# UniRF-Rev02.net
KiCad netlist of a schematic drawn in EAGLE
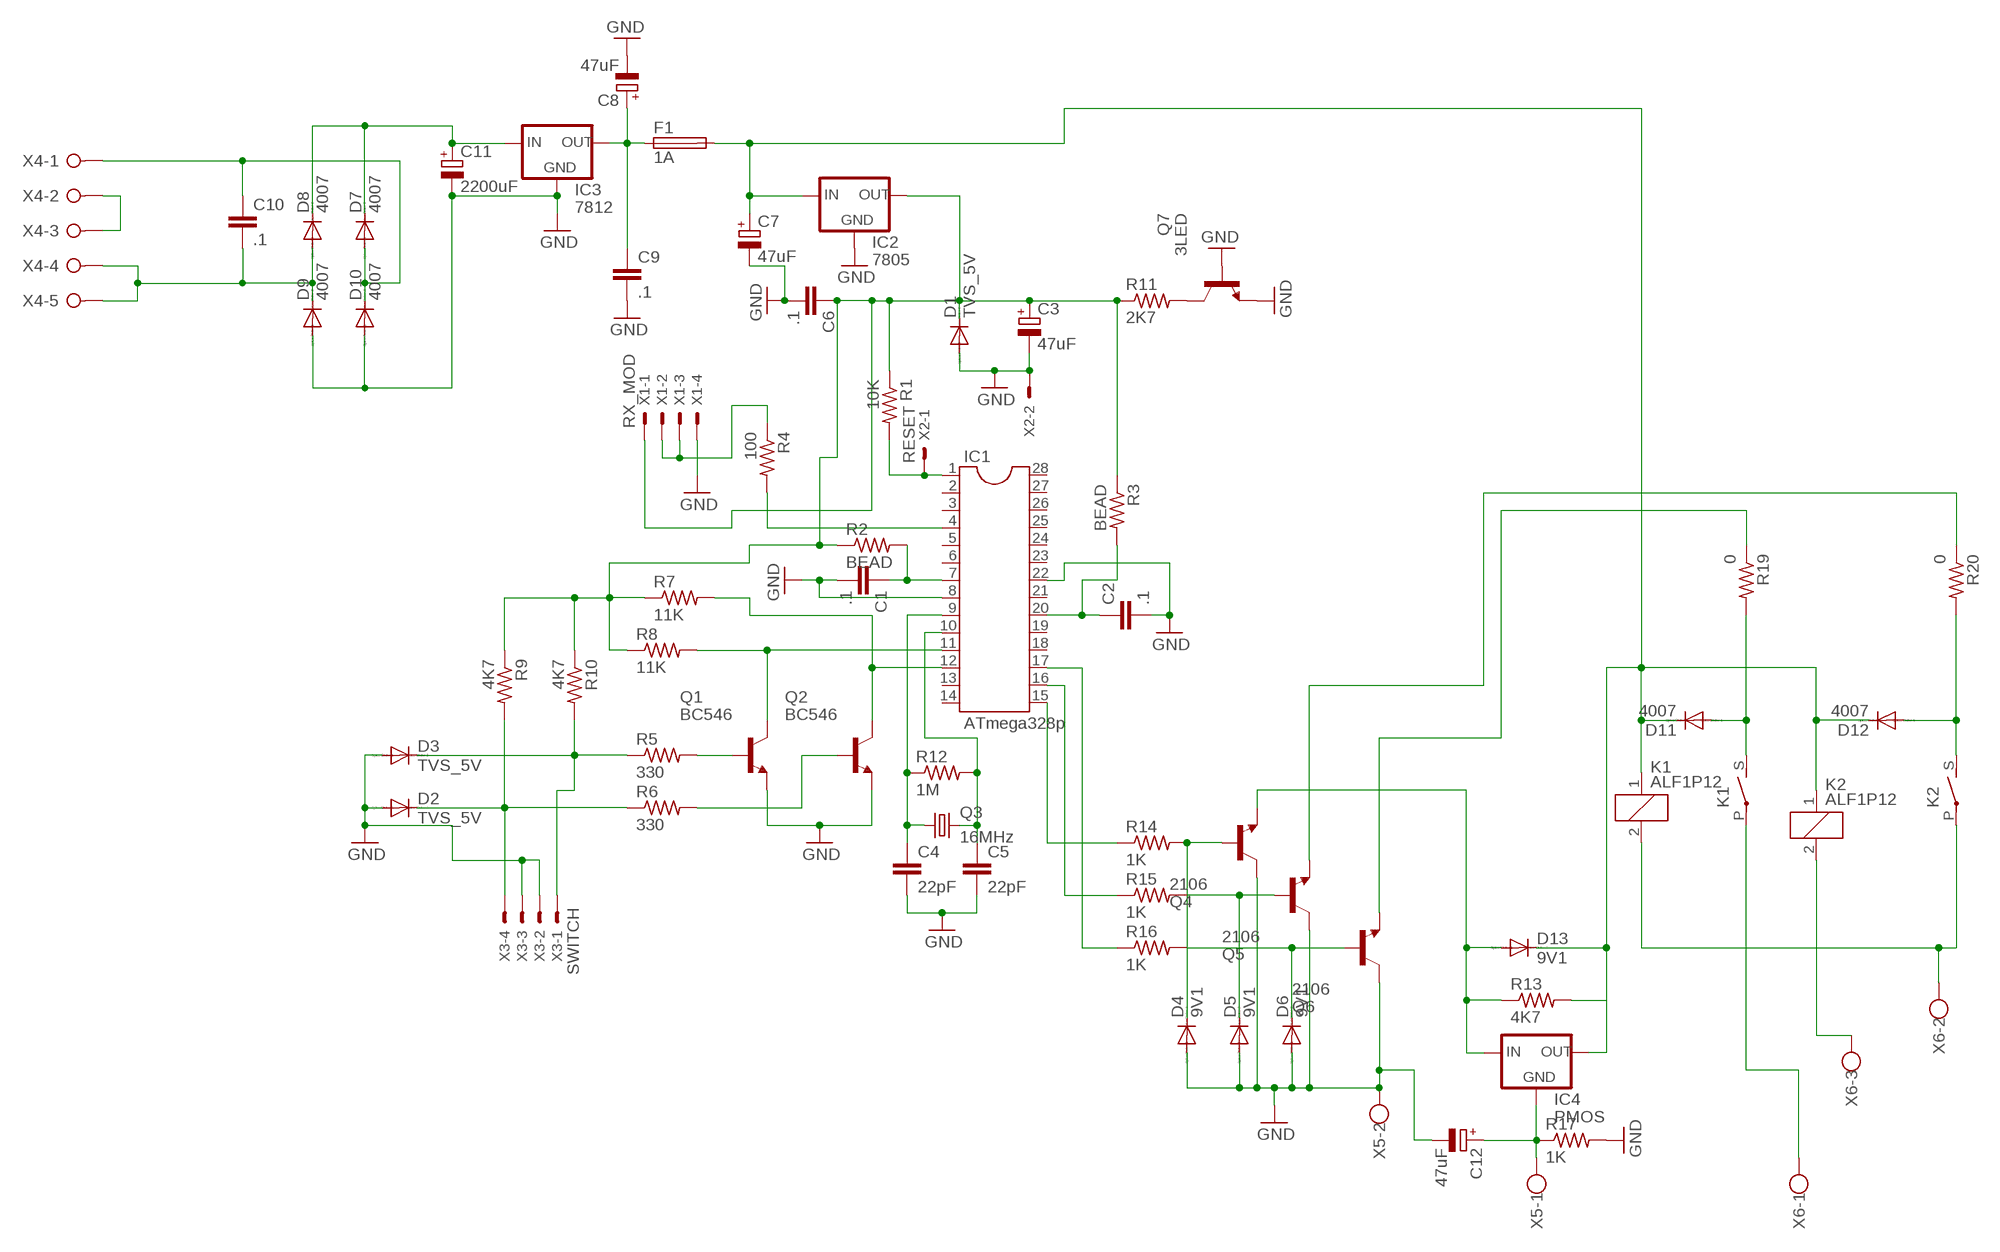
[diagram p0: schematic, sheet 1]

(export (version "E")
  (design (tool "Eeschema 10.0.6"))
  (components
    (comp (ref "C1")
      (value ".1")
      (footprint "eagle-import:C1210K")
      (libsource (lib "eagle-import") (part "C-EUC1210K"))
    )
    (comp (ref "C2")
      (value ".1")
      (footprint "eagle-import:C1210K")
      (libsource (lib "eagle-import") (part "C-EUC1210K"))
    )
    (comp (ref "C3")
      (value "47uF")
      (footprint "eagle-import:E5-8,5")
      (libsource (lib "eagle-import") (part "CPOL-EUE5-8.5"))
    )
    (comp (ref "C4")
      (value "22pF")
      (footprint "eagle-import:C1210K")
      (libsource (lib "eagle-import") (part "C-EUC1210K"))
    )
    (comp (ref "C5")
      (value "22pF")
      (footprint "eagle-import:C1210K")
      (libsource (lib "eagle-import") (part "C-EUC1210K"))
    )
    (comp (ref "C6")
      (value ".1")
      (footprint "eagle-import:C1210K")
      (libsource (lib "eagle-import") (part "C-EUC1210K"))
    )
    (comp (ref "C7")
      (value "47uF")
      (footprint "eagle-import:E5-8,5")
      (libsource (lib "eagle-import") (part "CPOL-EUE5-8.5"))
    )
    (comp (ref "C8")
      (value "47uF")
      (footprint "eagle-import:E5-8,5")
      (libsource (lib "eagle-import") (part "CPOL-EUE5-8.5"))
    )
    (comp (ref "C9")
      (value ".1")
      (footprint "eagle-import:C1210K")
      (libsource (lib "eagle-import") (part "C-EUC1210K"))
    )
    (comp (ref "C10")
      (value ".1")
      (footprint "eagle-import:C075-042X103")
      (libsource (lib "eagle-import") (part "C-EU075-042X103"))
    )
    (comp (ref "C11")
      (value "2200uF")
      (footprint "eagle-import:E7,5-18")
      (libsource (lib "eagle-import") (part "CPOL-EUE7.5-18"))
    )
    (comp (ref "C12")
      (value "47uF")
      (footprint "eagle-import:E5-8,5")
      (libsource (lib "eagle-import") (part "CPOL-EUE5-8.5"))
    )
    (comp (ref "D1")
      (value "TVS_5V")
      (footprint "eagle-import:DO35-10")
      (libsource (lib "eagle-import") (part "1N4148DO35-10"))
    )
    (comp (ref "D2")
      (value "TVS_5V")
      (footprint "eagle-import:DO35-10")
      (libsource (lib "eagle-import") (part "1N4148DO35-10"))
    )
    (comp (ref "D3")
      (value "TVS_5V")
      (footprint "eagle-import:DO35-10")
      (libsource (lib "eagle-import") (part "1N4148DO35-10"))
    )
    (comp (ref "D4")
      (value "9V1")
      (footprint "eagle-import:DO35-7")
      (libsource (lib "eagle-import") (part "1N4148DO35-7"))
    )
    (comp (ref "D5")
      (value "9V1")
      (footprint "eagle-import:DO35-7")
      (libsource (lib "eagle-import") (part "1N4148DO35-7"))
    )
    (comp (ref "D6")
      (value "9V1")
      (footprint "eagle-import:DO35-7")
      (libsource (lib "eagle-import") (part "1N4148DO35-7"))
    )
    (comp (ref "D7")
      (value "4007")
      (footprint "eagle-import:DO204-10")
      (libsource (lib "eagle-import") (part "1N5059"))
    )
    (comp (ref "D8")
      (value "4007")
      (footprint "eagle-import:DO204-10")
      (libsource (lib "eagle-import") (part "1N5059"))
    )
    (comp (ref "D9")
      (value "4007")
      (footprint "eagle-import:DO204-10")
      (libsource (lib "eagle-import") (part "1N5059"))
    )
    (comp (ref "D10")
      (value "4007")
      (footprint "eagle-import:DO204-10")
      (libsource (lib "eagle-import") (part "1N5059"))
    )
    (comp (ref "D11")
      (value "4007")
      (footprint "eagle-import:DO35-10")
      (libsource (lib "eagle-import") (part "1N4148DO35-10"))
    )
    (comp (ref "D12")
      (value "4007")
      (footprint "eagle-import:DO35-10")
      (libsource (lib "eagle-import") (part "1N4148DO35-10"))
    )
    (comp (ref "D13")
      (value "9V1")
      (footprint "eagle-import:DO35-10")
      (libsource (lib "eagle-import") (part "1N4148DO35-10"))
    )
    (comp (ref "F1")
      (value "1A")
      (footprint "eagle-import:19560")
      (fields (field (name "MPN") "56000001009"))
      (libsource (lib "eagle-import") (part "19560"))
    )
    (comp (ref "IC1")
      (value "ATmega328p")
      (footprint "eagle-import:DIL28-3")
      (libsource (lib "eagle-import") (part "DIL28-3"))
    )
    (comp (ref "IC2")
      (value "7805")
      (footprint "eagle-import:78XXS")
      (libsource (lib "eagle-import") (part "78XXS"))
    )
    (comp (ref "IC3")
      (value "7812")
      (footprint "eagle-import:78XXS")
      (libsource (lib "eagle-import") (part "78XXS"))
    )
    (comp (ref "IC4")
      (value "PMOS")
      (footprint "eagle-import:78XXS")
      (libsource (lib "eagle-import") (part "78XXS"))
    )
    (comp (ref "K1")
      (value "ALF1P12")
      (footprint "eagle-import:G2RA")
      (libsource (lib "eagle-import") (part "G2RA"))
    )
    (comp (ref "K2")
      (value "ALF1P12")
      (footprint "eagle-import:G2RA")
      (libsource (lib "eagle-import") (part "G2RA"))
    )
    (comp (ref "Q1")
      (value "BC546")
      (footprint "eagle-import:TO92-EBC")
      (libsource (lib "eagle-import") (part "BC546A"))
    )
    (comp (ref "Q2")
      (value "BC546")
      (footprint "eagle-import:TO92-EBC")
      (libsource (lib "eagle-import") (part "BC546A"))
    )
    (comp (ref "Q3")
      (value "16MHz")
      (footprint "eagle-import:HC49_S")
      (libsource (lib "eagle-import") (part "CRYSTALHC49S"))
    )
    (comp (ref "Q4")
      (value "2106")
      (footprint "eagle-import:TO92-EBC")
      (libsource (lib "eagle-import") (part "BC546A"))
    )
    (comp (ref "Q5")
      (value "2106")
      (footprint "eagle-import:TO92-EBC")
      (libsource (lib "eagle-import") (part "BC546A"))
    )
    (comp (ref "Q6")
      (value "2106")
      (footprint "eagle-import:TO92-EBC")
      (libsource (lib "eagle-import") (part "BC546A"))
    )
    (comp (ref "Q7")
      (value "3LED")
      (footprint "eagle-import:TO92-EBC")
      (libsource (lib "eagle-import") (part "BC546A"))
    )
    (comp (ref "R1")
      (value "10K")
      (footprint "eagle-import:0309_10")
      (libsource (lib "eagle-import") (part "R-US_0309/10"))
    )
    (comp (ref "R2")
      (value "BEAD")
      (footprint "eagle-import:0309_10")
      (libsource (lib "eagle-import") (part "R-US_0309/10"))
    )
    (comp (ref "R3")
      (value "BEAD")
      (footprint "eagle-import:0309_12")
      (libsource (lib "eagle-import") (part "R-US_0309/12"))
    )
    (comp (ref "R4")
      (value "100")
      (footprint "eagle-import:0309_10")
      (libsource (lib "eagle-import") (part "R-US_0309/10"))
    )
    (comp (ref "R5")
      (value "330")
      (footprint "eagle-import:0309_10")
      (libsource (lib "eagle-import") (part "R-US_0309/10"))
    )
    (comp (ref "R6")
      (value "330")
      (footprint "eagle-import:0309_10")
      (libsource (lib "eagle-import") (part "R-US_0309/10"))
    )
    (comp (ref "R7")
      (value "11K")
      (footprint "eagle-import:0309_10")
      (libsource (lib "eagle-import") (part "R-US_0309/10"))
    )
    (comp (ref "R8")
      (value "11K")
      (footprint "eagle-import:0309_10")
      (libsource (lib "eagle-import") (part "R-US_0309/10"))
    )
    (comp (ref "R9")
      (value "4K7")
      (footprint "eagle-import:0309_10")
      (libsource (lib "eagle-import") (part "R-US_0309/10"))
    )
    (comp (ref "R10")
      (value "4K7")
      (footprint "eagle-import:0309_10")
      (libsource (lib "eagle-import") (part "R-US_0309/10"))
    )
    (comp (ref "R11")
      (value "2K7")
      (footprint "eagle-import:0309_10")
      (libsource (lib "eagle-import") (part "R-US_0309/10"))
    )
    (comp (ref "R12")
      (value "1M")
      (footprint "eagle-import:0309V")
      (libsource (lib "eagle-import") (part "R-US_0309/V"))
    )
    (comp (ref "R13")
      (value "4K7")
      (footprint "eagle-import:0309_10")
      (libsource (lib "eagle-import") (part "R-US_0309/10"))
    )
    (comp (ref "R14")
      (value "1K")
      (footprint "eagle-import:R1210")
      (libsource (lib "eagle-import") (part "R-US_R1210"))
    )
    (comp (ref "R15")
      (value "1K")
      (footprint "eagle-import:R1210")
      (libsource (lib "eagle-import") (part "R-US_R1210"))
    )
    (comp (ref "R16")
      (value "1K")
      (footprint "eagle-import:R1210")
      (libsource (lib "eagle-import") (part "R-US_R1210"))
    )
    (comp (ref "R17")
      (value "1K")
      (footprint "eagle-import:0309_12")
      (libsource (lib "eagle-import") (part "R-US_0309/12"))
    )
    (comp (ref "R19")
      (value "0")
      (footprint "eagle-import:0207_12")
      (libsource (lib "eagle-import") (part "R-US_0207/12"))
    )
    (comp (ref "R20")
      (value "0")
      (footprint "eagle-import:0207_12")
      (libsource (lib "eagle-import") (part "R-US_0207/12"))
    )
    (comp (ref "X1")
      (value "RX_MOD")
      (footprint "eagle-import:22-23-2041")
      (fields (field (name "MF") "MOLEX") (field (name "MPN") "22-23-2041"))
      (libsource (lib "eagle-import") (part "22-23-2041"))
    )
    (comp (ref "X2")
      (value "RESET")
      (footprint "eagle-import:22-23-2021")
      (fields (field (name "MF") "MOLEX") (field (name "MPN") "22-23-2021"))
      (libsource (lib "eagle-import") (part "22-23-2021"))
    )
    (comp (ref "X3")
      (value "SWITCH")
      (footprint "eagle-import:22-23-2041")
      (fields (field (name "MF") "MOLEX") (field (name "MPN") "22-23-2041"))
      (libsource (lib "eagle-import") (part "22-23-2041"))
    )
    (comp (ref "X4")
      (value "W237-05P")
      (footprint "eagle-import:W237-5P")
      (libsource (lib "eagle-import") (part "W237-05P"))
    )
    (comp (ref "X5")
      (value "W237-102")
      (footprint "eagle-import:W237-102")
      (fields (field (name "MPN") "237-102"))
      (libsource (lib "eagle-import") (part "W237-102"))
    )
    (comp (ref "X6")
      (value "W237-103")
      (footprint "eagle-import:W237-103")
      (fields (field (name "MPN") "237-103"))
      (libsource (lib "eagle-import") (part "W237-103"))
    )
  )
  (nets
    (net (code "1") (name "GND") (class "Default")
      (node (ref "C1") (pin "2") (pinfunction "2_2") (pintype "passive"))
      (node (ref "C11") (pin "-") (pinfunction "-_-") (pintype "passive"))
      (node (ref "C12") (pin "-") (pinfunction "-_-") (pintype "passive"))
      (node (ref "C2") (pin "2") (pinfunction "2_2") (pintype "passive"))
      (node (ref "C3") (pin "-") (pinfunction "-_-") (pintype "passive"))
      (node (ref "C4") (pin "2") (pinfunction "2_2") (pintype "passive"))
      (node (ref "C5") (pin "2") (pinfunction "2_2") (pintype "passive"))
      (node (ref "C6") (pin "2") (pinfunction "2_2") (pintype "passive"))
      (node (ref "C7") (pin "-") (pinfunction "-_-") (pintype "passive"))
      (node (ref "C8") (pin "-") (pinfunction "-_-") (pintype "passive"))
      (node (ref "C9") (pin "2") (pinfunction "2_2") (pintype "passive"))
      (node (ref "D1") (pin "A") (pinfunction "A_A") (pintype "passive"))
      (node (ref "D10") (pin "A") (pinfunction "A_A") (pintype "passive"))
      (node (ref "D2") (pin "A") (pinfunction "A_A") (pintype "passive"))
      (node (ref "D3") (pin "A") (pinfunction "A_A") (pintype "passive"))
      (node (ref "D4") (pin "A") (pinfunction "A_A") (pintype "passive"))
      (node (ref "D5") (pin "A") (pinfunction "A_A") (pintype "passive"))
      (node (ref "D6") (pin "A") (pinfunction "A_A") (pintype "passive"))
      (node (ref "D9") (pin "A") (pinfunction "A_A") (pintype "passive"))
      (node (ref "IC1") (pin "22") (pinfunction "22_22") (pintype "passive"))
      (node (ref "IC1") (pin "8") (pinfunction "8_8") (pintype "passive"))
      (node (ref "IC2") (pin "GND") (pinfunction "GND_GND") (pintype "input"))
      (node (ref "IC3") (pin "GND") (pinfunction "GND_GND") (pintype "input"))
      (node (ref "Q1") (pin "E") (pinfunction "E_E") (pintype "passive"))
      (node (ref "Q2") (pin "E") (pinfunction "E_E") (pintype "passive"))
      (node (ref "Q4") (pin "C") (pinfunction "C_C") (pintype "passive"))
      (node (ref "Q5") (pin "C") (pinfunction "C_C") (pintype "passive"))
      (node (ref "Q6") (pin "C") (pinfunction "C_C") (pintype "passive"))
      (node (ref "Q7") (pin "B") (pinfunction "B_B") (pintype "passive"))
      (node (ref "Q7") (pin "E") (pinfunction "E_E") (pintype "passive"))
      (node (ref "R17") (pin "2") (pinfunction "2_2") (pintype "passive"))
      (node (ref "X1") (pin "4") (pinfunction "S_4") (pintype "passive"))
      (node (ref "X2") (pin "2") (pinfunction "S_2") (pintype "passive"))
      (node (ref "X3") (pin "2") (pinfunction "S_2") (pintype "passive"))
      (node (ref "X3") (pin "3") (pinfunction "S_3") (pintype "passive"))
      (node (ref "X5") (pin "2") (pinfunction "KL_2") (pintype "passive"))
    )
    (net (code "2") (name "Net-(C1-Pad1)") (class "Default")
      (node (ref "C1") (pin "1") (pinfunction "1_1") (pintype "passive"))
      (node (ref "IC1") (pin "7") (pinfunction "7_7") (pintype "passive"))
      (node (ref "R2") (pin "2") (pinfunction "2_2") (pintype "passive"))
    )
    (net (code "3") (name "Net-(C2-Pad1)") (class "Default")
      (node (ref "C2") (pin "1") (pinfunction "1_1") (pintype "passive"))
      (node (ref "IC1") (pin "20") (pinfunction "20_20") (pintype "passive"))
      (node (ref "R3") (pin "2") (pinfunction "2_2") (pintype "passive"))
    )
    (net (code "4") (name "Net-(C4-Pad1)") (class "Default")
      (node (ref "C4") (pin "1") (pinfunction "1_1") (pintype "passive"))
      (node (ref "IC1") (pin "9") (pinfunction "9_9") (pintype "passive"))
      (node (ref "Q3") (pin "1") (pinfunction "1_1") (pintype "passive"))
      (node (ref "R12") (pin "1") (pinfunction "1_1") (pintype "passive"))
    )
    (net (code "5") (name "Net-(C5-Pad1)") (class "Default")
      (node (ref "C5") (pin "1") (pinfunction "1_1") (pintype "passive"))
      (node (ref "IC1") (pin "10") (pinfunction "10_10") (pintype "passive"))
      (node (ref "Q3") (pin "2") (pinfunction "2_2") (pintype "passive"))
      (node (ref "R12") (pin "2") (pinfunction "2_2") (pintype "passive"))
    )
    (net (code "6") (name "Net-(C7-Pad+)") (class "Default")
      (node (ref "C7") (pin "+") (pinfunction "+_+") (pintype "passive"))
      (node (ref "D11") (pin "C") (pinfunction "C_C") (pintype "passive"))
      (node (ref "D12") (pin "C") (pinfunction "C_C") (pintype "passive"))
      (node (ref "D13") (pin "C") (pinfunction "C_C") (pintype "passive"))
      (node (ref "F1") (pin "2") (pinfunction "2_2") (pintype "passive"))
      (node (ref "IC2") (pin "IN") (pinfunction "IN_IN") (pintype "input"))
      (node (ref "IC4") (pin "OUT") (pinfunction "OUT_OUT") (pintype "passive"))
      (node (ref "K1") (pin "1") (pinfunction "1_1") (pintype "passive"))
      (node (ref "K2") (pin "1") (pinfunction "1_1") (pintype "passive"))
      (node (ref "R13") (pin "2") (pinfunction "2_2") (pintype "passive"))
    )
    (net (code "7") (name "Net-(C8-Pad+)") (class "Default")
      (node (ref "C8") (pin "+") (pinfunction "+_+") (pintype "passive"))
      (node (ref "C9") (pin "1") (pinfunction "1_1") (pintype "passive"))
      (node (ref "F1") (pin "1") (pinfunction "1_1") (pintype "passive"))
      (node (ref "IC3") (pin "OUT") (pinfunction "OUT_OUT") (pintype "passive"))
    )
    (net (code "8") (name "Net-(C11-Pad+)") (class "Default")
      (node (ref "C11") (pin "+") (pinfunction "+_+") (pintype "passive"))
      (node (ref "D7") (pin "C") (pinfunction "C_C") (pintype "passive"))
      (node (ref "D8") (pin "C") (pinfunction "C_C") (pintype "passive"))
      (node (ref "IC3") (pin "IN") (pinfunction "IN_IN") (pintype "input"))
    )
    (net (code "9") (name "Net-(D4-PadC)") (class "Default")
      (node (ref "D4") (pin "C") (pinfunction "C_C") (pintype "passive"))
      (node (ref "Q4") (pin "B") (pinfunction "B_B") (pintype "passive"))
      (node (ref "R14") (pin "2") (pinfunction "2_2") (pintype "passive"))
    )
    (net (code "10") (name "Net-(D5-PadC)") (class "Default")
      (node (ref "D5") (pin "C") (pinfunction "C_C") (pintype "passive"))
      (node (ref "Q5") (pin "B") (pinfunction "B_B") (pintype "passive"))
      (node (ref "R15") (pin "2") (pinfunction "2_2") (pintype "passive"))
    )
    (net (code "11") (name "Net-(D6-PadC)") (class "Default")
      (node (ref "D6") (pin "C") (pinfunction "C_C") (pintype "passive"))
      (node (ref "Q6") (pin "B") (pinfunction "B_B") (pintype "passive"))
      (node (ref "R16") (pin "2") (pinfunction "2_2") (pintype "passive"))
    )
    (net (code "12") (name "Net-(D11-PadA)") (class "Default")
      (node (ref "D11") (pin "A") (pinfunction "A_A") (pintype "passive"))
      (node (ref "K1") (pin "S") (pinfunction "S_S") (pintype "passive"))
      (node (ref "R19") (pin "2") (pinfunction "2_2") (pintype "passive"))
    )
    (net (code "13") (name "Net-(D12-PadA)") (class "Default")
      (node (ref "D12") (pin "A") (pinfunction "A_A") (pintype "passive"))
      (node (ref "K2") (pin "S") (pinfunction "S_S") (pintype "passive"))
      (node (ref "R20") (pin "2") (pinfunction "2_2") (pintype "passive"))
    )
    (net (code "14") (name "Net-(D13-PadA)") (class "Default")
      (node (ref "D13") (pin "A") (pinfunction "A_A") (pintype "passive"))
      (node (ref "IC4") (pin "IN") (pinfunction "IN_IN") (pintype "input"))
      (node (ref "Q4") (pin "E") (pinfunction "E_E") (pintype "passive"))
      (node (ref "R13") (pin "1") (pinfunction "1_1") (pintype "passive"))
    )
    (net (code "15") (name "Net-(IC1-Pad4)") (class "Default")
      (node (ref "IC1") (pin "4") (pinfunction "4_4") (pintype "passive"))
      (node (ref "R4") (pin "2") (pinfunction "2_2") (pintype "passive"))
    )
    (net (code "16") (name "Net-(IC1-Pad11)") (class "Default")
      (node (ref "IC1") (pin "11") (pinfunction "11_11") (pintype "passive"))
      (node (ref "Q1") (pin "C") (pinfunction "C_C") (pintype "passive"))
      (node (ref "R8") (pin "2") (pinfunction "2_2") (pintype "passive"))
    )
    (net (code "17") (name "Net-(IC1-Pad12)") (class "Default")
      (node (ref "IC1") (pin "12") (pinfunction "12_12") (pintype "passive"))
      (node (ref "Q2") (pin "C") (pinfunction "C_C") (pintype "passive"))
      (node (ref "R7") (pin "2") (pinfunction "2_2") (pintype "passive"))
    )
    (net (code "18") (name "Net-(IC1-Pad15)") (class "Default")
      (node (ref "IC1") (pin "15") (pinfunction "15_15") (pintype "passive"))
      (node (ref "R14") (pin "1") (pinfunction "1_1") (pintype "passive"))
    )
    (net (code "19") (name "Net-(IC1-Pad16)") (class "Default")
      (node (ref "IC1") (pin "16") (pinfunction "16_16") (pintype "passive"))
      (node (ref "R15") (pin "1") (pinfunction "1_1") (pintype "passive"))
    )
    (net (code "20") (name "Net-(IC1-Pad17)") (class "Default")
      (node (ref "IC1") (pin "17") (pinfunction "17_17") (pintype "passive"))
      (node (ref "R16") (pin "1") (pinfunction "1_1") (pintype "passive"))
    )
    (net (code "21") (name "Net-(Q1-PadB)") (class "Default")
      (node (ref "Q1") (pin "B") (pinfunction "B_B") (pintype "passive"))
      (node (ref "R5") (pin "2") (pinfunction "2_2") (pintype "passive"))
    )
    (net (code "22") (name "Net-(Q2-PadB)") (class "Default")
      (node (ref "Q2") (pin "B") (pinfunction "B_B") (pintype "passive"))
      (node (ref "R6") (pin "2") (pinfunction "2_2") (pintype "passive"))
    )
    (net (code "23") (name "Net-(Q5-PadE)") (class "Default")
      (node (ref "Q5") (pin "E") (pinfunction "E_E") (pintype "passive"))
      (node (ref "R20") (pin "1") (pinfunction "1_1") (pintype "passive"))
    )
    (net (code "24") (name "Net-(Q6-PadE)") (class "Default")
      (node (ref "Q6") (pin "E") (pinfunction "E_E") (pintype "passive"))
      (node (ref "R19") (pin "1") (pinfunction "1_1") (pintype "passive"))
    )
    (net (code "25") (name "Net-(Q7-PadC)") (class "Default")
      (node (ref "Q7") (pin "C") (pinfunction "C_C") (pintype "passive"))
      (node (ref "R11") (pin "2") (pinfunction "2_2") (pintype "passive"))
    )
    (net (code "26") (name "Net-(X1A-S)") (class "Default")
      (node (ref "C3") (pin "+") (pinfunction "+_+") (pintype "passive"))
      (node (ref "C6") (pin "1") (pinfunction "1_1") (pintype "passive"))
      (node (ref "D1") (pin "C") (pinfunction "C_C") (pintype "passive"))
      (node (ref "IC2") (pin "OUT") (pinfunction "OUT_OUT") (pintype "passive"))
      (node (ref "R1") (pin "1") (pinfunction "1_1") (pintype "passive"))
      (node (ref "R10") (pin "1") (pinfunction "1_1") (pintype "passive"))
      (node (ref "R11") (pin "1") (pinfunction "1_1") (pintype "passive"))
      (node (ref "R2") (pin "1") (pinfunction "1_1") (pintype "passive"))
      (node (ref "R3") (pin "1") (pinfunction "1_1") (pintype "passive"))
      (node (ref "R7") (pin "1") (pinfunction "1_1") (pintype "passive"))
      (node (ref "R8") (pin "1") (pinfunction "1_1") (pintype "passive"))
      (node (ref "R9") (pin "1") (pinfunction "1_1") (pintype "passive"))
      (node (ref "X1") (pin "1") (pinfunction "S_1") (pintype "passive"))
    )
    (net (code "27") (name "Net-(X1B-S)") (class "Default")
      (node (ref "R4") (pin "1") (pinfunction "1_1") (pintype "passive"))
      (node (ref "X1") (pin "2") (pinfunction "S_2") (pintype "passive"))
      (node (ref "X1") (pin "3") (pinfunction "S_3") (pintype "passive"))
    )
    (net (code "28") (name "Net-(X2A-S)") (class "Default")
      (node (ref "IC1") (pin "1") (pinfunction "1_1") (pintype "passive"))
      (node (ref "R1") (pin "2") (pinfunction "2_2") (pintype "passive"))
      (node (ref "X2") (pin "1") (pinfunction "S_1") (pintype "passive"))
    )
    (net (code "29") (name "Net-(X3A-S)") (class "Default")
      (node (ref "D3") (pin "C") (pinfunction "C_C") (pintype "passive"))
      (node (ref "R10") (pin "2") (pinfunction "2_2") (pintype "passive"))
      (node (ref "R5") (pin "1") (pinfunction "1_1") (pintype "passive"))
      (node (ref "X3") (pin "1") (pinfunction "S_1") (pintype "passive"))
    )
    (net (code "30") (name "Net-(X3D-S)") (class "Default")
      (node (ref "D2") (pin "C") (pinfunction "C_C") (pintype "passive"))
      (node (ref "R6") (pin "1") (pinfunction "1_1") (pintype "passive"))
      (node (ref "R9") (pin "2") (pinfunction "2_2") (pintype "passive"))
      (node (ref "X3") (pin "4") (pinfunction "S_4") (pintype "passive"))
    )
    (net (code "31") (name "Net-(X4A-KL)") (class "Default")
      (node (ref "C10") (pin "1") (pinfunction "1_1") (pintype "passive"))
      (node (ref "D10") (pin "C") (pinfunction "C_C") (pintype "passive"))
      (node (ref "D7") (pin "A") (pinfunction "A_A") (pintype "passive"))
      (node (ref "X4") (pin "1") (pinfunction "KL_1") (pintype "passive"))
    )
    (net (code "32") (name "Net-(X4B-KL)") (class "Default")
      (node (ref "X4") (pin "2") (pinfunction "KL_2") (pintype "passive"))
      (node (ref "X4") (pin "3") (pinfunction "KL_3") (pintype "passive"))
    )
    (net (code "33") (name "Net-(X4D-KL)") (class "Default")
      (node (ref "C10") (pin "2") (pinfunction "2_2") (pintype "passive"))
      (node (ref "D8") (pin "A") (pinfunction "A_A") (pintype "passive"))
      (node (ref "D9") (pin "C") (pinfunction "C_C") (pintype "passive"))
      (node (ref "X4") (pin "4") (pinfunction "KL_4") (pintype "passive"))
      (node (ref "X4") (pin "5") (pinfunction "KL_5") (pintype "passive"))
    )
    (net (code "34") (name "Net-(X5A-KL)") (class "Default")
      (node (ref "C12") (pin "+") (pinfunction "+_+") (pintype "passive"))
      (node (ref "IC4") (pin "GND") (pinfunction "GND_GND") (pintype "input"))
      (node (ref "R17") (pin "1") (pinfunction "1_1") (pintype "passive"))
      (node (ref "X5") (pin "1") (pinfunction "KL_1") (pintype "passive"))
    )
    (net (code "35") (name "Net-(X6A-KL)") (class "Default")
      (node (ref "K1") (pin "P") (pinfunction "P_P") (pintype "passive"))
      (node (ref "X6") (pin "1") (pinfunction "KL_1") (pintype "passive"))
    )
    (net (code "36") (name "Net-(X6B-KL)") (class "Default")
      (node (ref "K1") (pin "2") (pinfunction "2_2") (pintype "passive"))
      (node (ref "K2") (pin "P") (pinfunction "P_P") (pintype "passive"))
      (node (ref "X6") (pin "2") (pinfunction "KL_2") (pintype "passive"))
    )
    (net (code "37") (name "Net-(X6C-KL)") (class "Default")
      (node (ref "K2") (pin "2") (pinfunction "2_2") (pintype "passive"))
      (node (ref "X6") (pin "3") (pinfunction "KL_3") (pintype "passive"))
    )
    (net (code "38") (name "unconnected-(IC1-Pad2)") (class "Default")
      (node (ref "IC1") (pin "2") (pinfunction "2_2") (pintype "passive"))
    )
    (net (code "39") (name "unconnected-(IC1-Pad3)") (class "Default")
      (node (ref "IC1") (pin "3") (pinfunction "3_3") (pintype "passive"))
    )
    (net (code "40") (name "unconnected-(IC1-Pad5)") (class "Default")
      (node (ref "IC1") (pin "5") (pinfunction "5_5") (pintype "passive"))
    )
    (net (code "41") (name "unconnected-(IC1-Pad6)") (class "Default")
      (node (ref "IC1") (pin "6") (pinfunction "6_6") (pintype "passive"))
    )
    (net (code "42") (name "unconnected-(IC1-Pad13)") (class "Default")
      (node (ref "IC1") (pin "13") (pinfunction "13_13") (pintype "passive"))
    )
    (net (code "43") (name "unconnected-(IC1-Pad14)") (class "Default")
      (node (ref "IC1") (pin "14") (pinfunction "14_14") (pintype "passive"))
    )
    (net (code "44") (name "unconnected-(IC1-Pad18)") (class "Default")
      (node (ref "IC1") (pin "18") (pinfunction "18_18") (pintype "passive"))
    )
    (net (code "45") (name "unconnected-(IC1-Pad19)") (class "Default")
      (node (ref "IC1") (pin "19") (pinfunction "19_19") (pintype "passive"))
    )
    (net (code "46") (name "unconnected-(IC1-Pad21)") (class "Default")
      (node (ref "IC1") (pin "21") (pinfunction "21_21") (pintype "passive"))
    )
    (net (code "47") (name "unconnected-(IC1-Pad23)") (class "Default")
      (node (ref "IC1") (pin "23") (pinfunction "23_23") (pintype "passive"))
    )
    (net (code "48") (name "unconnected-(IC1-Pad24)") (class "Default")
      (node (ref "IC1") (pin "24") (pinfunction "24_24") (pintype "passive"))
    )
    (net (code "49") (name "unconnected-(IC1-Pad25)") (class "Default")
      (node (ref "IC1") (pin "25") (pinfunction "25_25") (pintype "passive"))
    )
    (net (code "50") (name "unconnected-(IC1-Pad26)") (class "Default")
      (node (ref "IC1") (pin "26") (pinfunction "26_26") (pintype "passive"))
    )
    (net (code "51") (name "unconnected-(IC1-Pad27)") (class "Default")
      (node (ref "IC1") (pin "27") (pinfunction "27_27") (pintype "passive"))
    )
    (net (code "52") (name "unconnected-(IC1-Pad28)") (class "Default")
      (node (ref "IC1") (pin "28") (pinfunction "28_28") (pintype "passive"))
    )
  )
)
